# schematic_v2.net
KiCad netlist of a schematic drawn in EAGLE
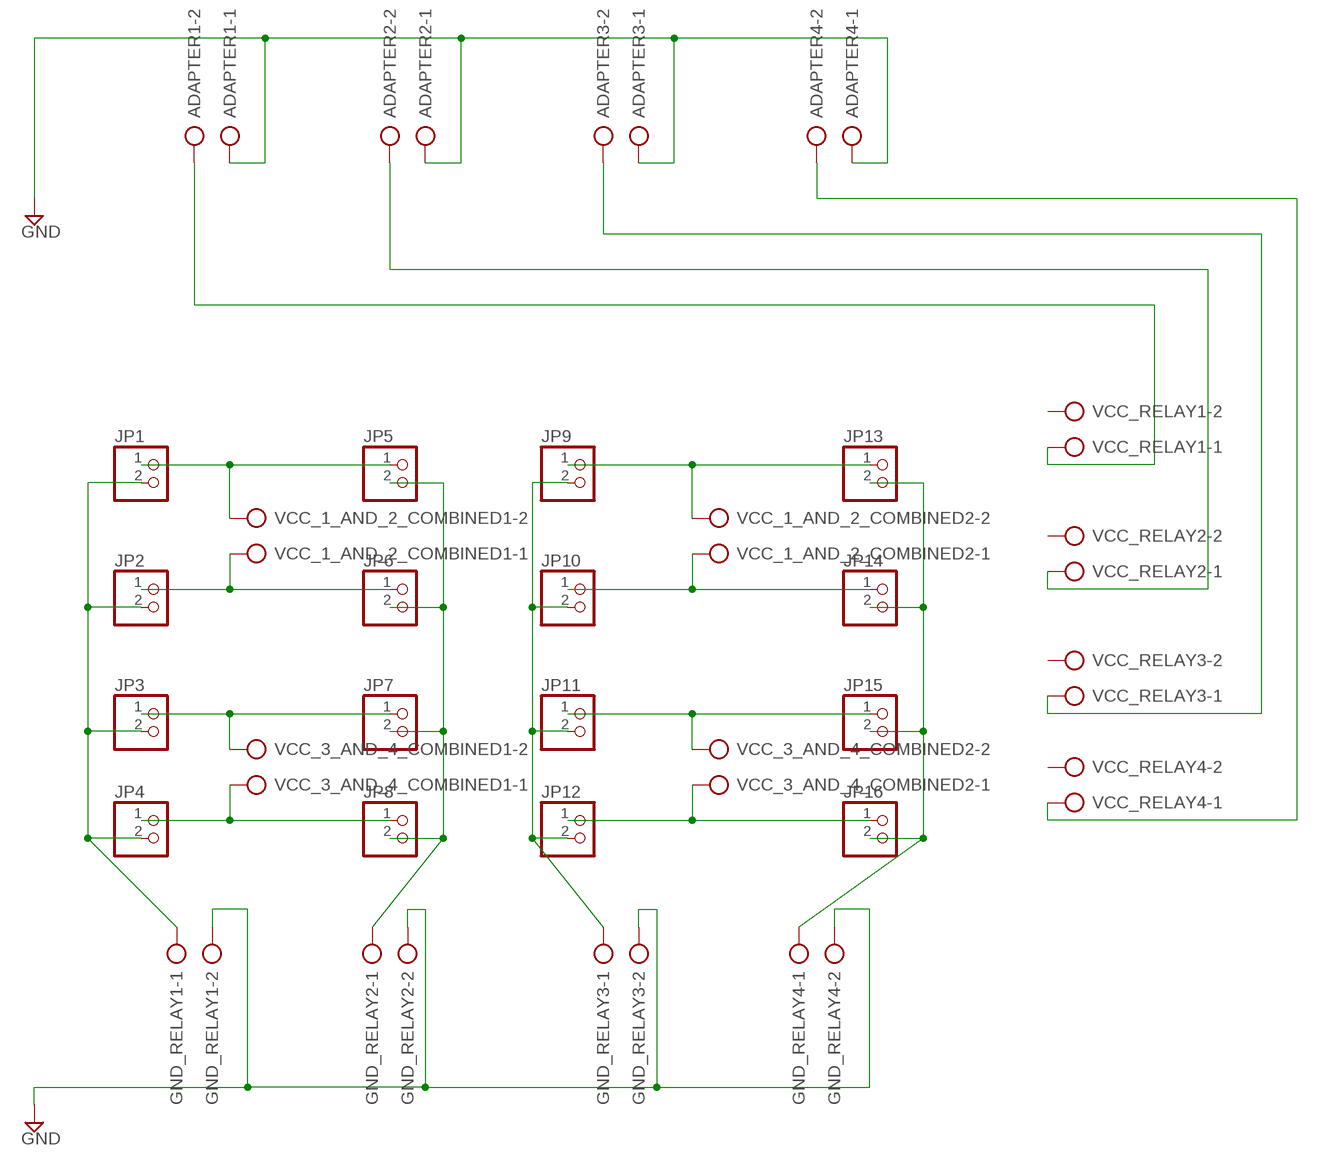
[diagram p0: schematic, sheet 1]

(export (version "E")
  (design (tool "Eeschema 10.0.6"))
  (components
    (comp (ref "ADAPTER1")
      (value "AK300/2")
      (footprint "eagle-import:AK300_2")
      (libsource (lib "eagle-import") (part "AK300/2"))
    )
    (comp (ref "ADAPTER2")
      (value "AK300/2")
      (footprint "eagle-import:AK300_2")
      (libsource (lib "eagle-import") (part "AK300/2"))
    )
    (comp (ref "ADAPTER3")
      (value "AK300/2")
      (footprint "eagle-import:AK300_2")
      (libsource (lib "eagle-import") (part "AK300/2"))
    )
    (comp (ref "ADAPTER4")
      (value "AK300/2")
      (footprint "eagle-import:AK300_2")
      (libsource (lib "eagle-import") (part "AK300/2"))
    )
    (comp (ref "GND_RELAY1")
      (value "AK300/2")
      (footprint "eagle-import:AK300_2")
      (libsource (lib "eagle-import") (part "AK300/2"))
    )
    (comp (ref "GND_RELAY2")
      (value "AK300/2")
      (footprint "eagle-import:AK300_2")
      (libsource (lib "eagle-import") (part "AK300/2"))
    )
    (comp (ref "GND_RELAY3")
      (value "AK300/2")
      (footprint "eagle-import:AK300_2")
      (libsource (lib "eagle-import") (part "AK300/2"))
    )
    (comp (ref "GND_RELAY4")
      (value "AK300/2")
      (footprint "eagle-import:AK300_2")
      (libsource (lib "eagle-import") (part "AK300/2"))
    )
    (comp (ref "JP1")
      (value "PINHD-1X2")
      (footprint "eagle-import:1X02")
      (libsource (lib "eagle-import") (part "PINHD-1X2"))
    )
    (comp (ref "JP2")
      (value "PINHD-1X2")
      (footprint "eagle-import:1X02")
      (libsource (lib "eagle-import") (part "PINHD-1X2"))
    )
    (comp (ref "JP3")
      (value "PINHD-1X2")
      (footprint "eagle-import:1X02")
      (libsource (lib "eagle-import") (part "PINHD-1X2"))
    )
    (comp (ref "JP4")
      (value "PINHD-1X2")
      (footprint "eagle-import:1X02")
      (libsource (lib "eagle-import") (part "PINHD-1X2"))
    )
    (comp (ref "JP5")
      (value "PINHD-1X2")
      (footprint "eagle-import:1X02")
      (libsource (lib "eagle-import") (part "PINHD-1X2"))
    )
    (comp (ref "JP6")
      (value "PINHD-1X2")
      (footprint "eagle-import:1X02")
      (libsource (lib "eagle-import") (part "PINHD-1X2"))
    )
    (comp (ref "JP7")
      (value "PINHD-1X2")
      (footprint "eagle-import:1X02")
      (libsource (lib "eagle-import") (part "PINHD-1X2"))
    )
    (comp (ref "JP8")
      (value "PINHD-1X2")
      (footprint "eagle-import:1X02")
      (libsource (lib "eagle-import") (part "PINHD-1X2"))
    )
    (comp (ref "JP9")
      (value "PINHD-1X2")
      (footprint "eagle-import:1X02")
      (libsource (lib "eagle-import") (part "PINHD-1X2"))
    )
    (comp (ref "JP10")
      (value "PINHD-1X2")
      (footprint "eagle-import:1X02")
      (libsource (lib "eagle-import") (part "PINHD-1X2"))
    )
    (comp (ref "JP11")
      (value "PINHD-1X2")
      (footprint "eagle-import:1X02")
      (libsource (lib "eagle-import") (part "PINHD-1X2"))
    )
    (comp (ref "JP12")
      (value "PINHD-1X2")
      (footprint "eagle-import:1X02")
      (libsource (lib "eagle-import") (part "PINHD-1X2"))
    )
    (comp (ref "JP13")
      (value "PINHD-1X2")
      (footprint "eagle-import:1X02")
      (libsource (lib "eagle-import") (part "PINHD-1X2"))
    )
    (comp (ref "JP14")
      (value "PINHD-1X2")
      (footprint "eagle-import:1X02")
      (libsource (lib "eagle-import") (part "PINHD-1X2"))
    )
    (comp (ref "JP15")
      (value "PINHD-1X2")
      (footprint "eagle-import:1X02")
      (libsource (lib "eagle-import") (part "PINHD-1X2"))
    )
    (comp (ref "JP16")
      (value "PINHD-1X2")
      (footprint "eagle-import:1X02")
      (libsource (lib "eagle-import") (part "PINHD-1X2"))
    )
    (comp (ref "VCC_1_AND_2_COMBINED1")
      (value "AK300/2")
      (footprint "eagle-import:AK300_2")
      (libsource (lib "eagle-import") (part "AK300/2"))
    )
    (comp (ref "VCC_1_AND_2_COMBINED2")
      (value "AK300/2")
      (footprint "eagle-import:AK300_2")
      (libsource (lib "eagle-import") (part "AK300/2"))
    )
    (comp (ref "VCC_3_AND_4_COMBINED1")
      (value "AK300/2")
      (footprint "eagle-import:AK300_2")
      (libsource (lib "eagle-import") (part "AK300/2"))
    )
    (comp (ref "VCC_3_AND_4_COMBINED2")
      (value "AK300/2")
      (footprint "eagle-import:AK300_2")
      (libsource (lib "eagle-import") (part "AK300/2"))
    )
    (comp (ref "VCC_RELAY1")
      (value "AK300/2")
      (footprint "eagle-import:AK300_2")
      (libsource (lib "eagle-import") (part "AK300/2"))
    )
    (comp (ref "VCC_RELAY2")
      (value "AK300/2")
      (footprint "eagle-import:AK300_2")
      (libsource (lib "eagle-import") (part "AK300/2"))
    )
    (comp (ref "VCC_RELAY3")
      (value "AK300/2")
      (footprint "eagle-import:AK300_2")
      (libsource (lib "eagle-import") (part "AK300/2"))
    )
    (comp (ref "VCC_RELAY4")
      (value "AK300/2")
      (footprint "eagle-import:AK300_2")
      (libsource (lib "eagle-import") (part "AK300/2"))
    )
  )
  (nets
    (net (code "1") (name "GND") (class "Default")
      (node (ref "ADAPTER1") (pin "1") (pinfunction "KL_1") (pintype "passive"))
      (node (ref "ADAPTER2") (pin "1") (pinfunction "KL_1") (pintype "passive"))
      (node (ref "ADAPTER3") (pin "1") (pinfunction "KL_1") (pintype "passive"))
      (node (ref "ADAPTER4") (pin "1") (pinfunction "KL_1") (pintype "passive"))
      (node (ref "GND_RELAY1") (pin "2") (pinfunction "KL_2") (pintype "passive"))
      (node (ref "GND_RELAY2") (pin "2") (pinfunction "KL_2") (pintype "passive"))
      (node (ref "GND_RELAY3") (pin "2") (pinfunction "KL_2") (pintype "passive"))
      (node (ref "GND_RELAY4") (pin "2") (pinfunction "KL_2") (pintype "passive"))
    )
    (net (code "2") (name "Net-(ADAPTER1B-KL)") (class "Default")
      (node (ref "ADAPTER1") (pin "2") (pinfunction "KL_2") (pintype "passive"))
      (node (ref "VCC_RELAY1") (pin "1") (pinfunction "KL_1") (pintype "passive"))
    )
    (net (code "3") (name "Net-(ADAPTER2B-KL)") (class "Default")
      (node (ref "ADAPTER2") (pin "2") (pinfunction "KL_2") (pintype "passive"))
      (node (ref "VCC_RELAY2") (pin "1") (pinfunction "KL_1") (pintype "passive"))
    )
    (net (code "4") (name "Net-(ADAPTER3B-KL)") (class "Default")
      (node (ref "ADAPTER3") (pin "2") (pinfunction "KL_2") (pintype "passive"))
      (node (ref "VCC_RELAY3") (pin "1") (pinfunction "KL_1") (pintype "passive"))
    )
    (net (code "5") (name "Net-(ADAPTER4B-KL)") (class "Default")
      (node (ref "ADAPTER4") (pin "2") (pinfunction "KL_2") (pintype "passive"))
      (node (ref "VCC_RELAY4") (pin "1") (pinfunction "KL_1") (pintype "passive"))
    )
    (net (code "6") (name "Net-(GND_RELAY1A-KL)") (class "Default")
      (node (ref "GND_RELAY1") (pin "1") (pinfunction "KL_1") (pintype "passive"))
      (node (ref "JP1") (pin "2") (pinfunction "2_2") (pintype "passive"))
      (node (ref "JP2") (pin "2") (pinfunction "2_2") (pintype "passive"))
      (node (ref "JP3") (pin "2") (pinfunction "2_2") (pintype "passive"))
      (node (ref "JP4") (pin "2") (pinfunction "2_2") (pintype "passive"))
    )
    (net (code "7") (name "Net-(GND_RELAY2A-KL)") (class "Default")
      (node (ref "GND_RELAY2") (pin "1") (pinfunction "KL_1") (pintype "passive"))
      (node (ref "JP5") (pin "2") (pinfunction "2_2") (pintype "passive"))
      (node (ref "JP6") (pin "2") (pinfunction "2_2") (pintype "passive"))
      (node (ref "JP7") (pin "2") (pinfunction "2_2") (pintype "passive"))
      (node (ref "JP8") (pin "2") (pinfunction "2_2") (pintype "passive"))
    )
    (net (code "8") (name "Net-(GND_RELAY3A-KL)") (class "Default")
      (node (ref "GND_RELAY3") (pin "1") (pinfunction "KL_1") (pintype "passive"))
      (node (ref "JP10") (pin "2") (pinfunction "2_2") (pintype "passive"))
      (node (ref "JP11") (pin "2") (pinfunction "2_2") (pintype "passive"))
      (node (ref "JP12") (pin "2") (pinfunction "2_2") (pintype "passive"))
      (node (ref "JP9") (pin "2") (pinfunction "2_2") (pintype "passive"))
    )
    (net (code "9") (name "Net-(GND_RELAY4A-KL)") (class "Default")
      (node (ref "GND_RELAY4") (pin "1") (pinfunction "KL_1") (pintype "passive"))
      (node (ref "JP13") (pin "2") (pinfunction "2_2") (pintype "passive"))
      (node (ref "JP14") (pin "2") (pinfunction "2_2") (pintype "passive"))
      (node (ref "JP15") (pin "2") (pinfunction "2_2") (pintype "passive"))
      (node (ref "JP16") (pin "2") (pinfunction "2_2") (pintype "passive"))
    )
    (net (code "10") (name "Net-(VCC_1_AND_2_COMBINED1A-KL)") (class "Default")
      (node (ref "JP2") (pin "1") (pinfunction "1_1") (pintype "passive"))
      (node (ref "JP6") (pin "1") (pinfunction "1_1") (pintype "passive"))
      (node (ref "VCC_1_AND_2_COMBINED1") (pin "1") (pinfunction "KL_1") (pintype "passive"))
    )
    (net (code "11") (name "Net-(VCC_1_AND_2_COMBINED1B-KL)") (class "Default")
      (node (ref "JP1") (pin "1") (pinfunction "1_1") (pintype "passive"))
      (node (ref "JP5") (pin "1") (pinfunction "1_1") (pintype "passive"))
      (node (ref "VCC_1_AND_2_COMBINED1") (pin "2") (pinfunction "KL_2") (pintype "passive"))
    )
    (net (code "12") (name "Net-(VCC_1_AND_2_COMBINED2A-KL)") (class "Default")
      (node (ref "JP10") (pin "1") (pinfunction "1_1") (pintype "passive"))
      (node (ref "JP14") (pin "1") (pinfunction "1_1") (pintype "passive"))
      (node (ref "VCC_1_AND_2_COMBINED2") (pin "1") (pinfunction "KL_1") (pintype "passive"))
    )
    (net (code "13") (name "Net-(VCC_1_AND_2_COMBINED2B-KL)") (class "Default")
      (node (ref "JP13") (pin "1") (pinfunction "1_1") (pintype "passive"))
      (node (ref "JP9") (pin "1") (pinfunction "1_1") (pintype "passive"))
      (node (ref "VCC_1_AND_2_COMBINED2") (pin "2") (pinfunction "KL_2") (pintype "passive"))
    )
    (net (code "14") (name "Net-(VCC_3_AND_4_COMBINED1A-KL)") (class "Default")
      (node (ref "JP4") (pin "1") (pinfunction "1_1") (pintype "passive"))
      (node (ref "JP8") (pin "1") (pinfunction "1_1") (pintype "passive"))
      (node (ref "VCC_3_AND_4_COMBINED1") (pin "1") (pinfunction "KL_1") (pintype "passive"))
    )
    (net (code "15") (name "Net-(VCC_3_AND_4_COMBINED1B-KL)") (class "Default")
      (node (ref "JP3") (pin "1") (pinfunction "1_1") (pintype "passive"))
      (node (ref "JP7") (pin "1") (pinfunction "1_1") (pintype "passive"))
      (node (ref "VCC_3_AND_4_COMBINED1") (pin "2") (pinfunction "KL_2") (pintype "passive"))
    )
    (net (code "16") (name "Net-(VCC_3_AND_4_COMBINED2A-KL)") (class "Default")
      (node (ref "JP12") (pin "1") (pinfunction "1_1") (pintype "passive"))
      (node (ref "JP16") (pin "1") (pinfunction "1_1") (pintype "passive"))
      (node (ref "VCC_3_AND_4_COMBINED2") (pin "1") (pinfunction "KL_1") (pintype "passive"))
    )
    (net (code "17") (name "Net-(VCC_3_AND_4_COMBINED2B-KL)") (class "Default")
      (node (ref "JP11") (pin "1") (pinfunction "1_1") (pintype "passive"))
      (node (ref "JP15") (pin "1") (pinfunction "1_1") (pintype "passive"))
      (node (ref "VCC_3_AND_4_COMBINED2") (pin "2") (pinfunction "KL_2") (pintype "passive"))
    )
    (net (code "18") (name "unconnected-(VCC_RELAY1B-KL-Pad2)") (class "Default")
      (node (ref "VCC_RELAY1") (pin "2") (pinfunction "KL_2") (pintype "passive"))
    )
    (net (code "19") (name "unconnected-(VCC_RELAY2B-KL-Pad2)") (class "Default")
      (node (ref "VCC_RELAY2") (pin "2") (pinfunction "KL_2") (pintype "passive"))
    )
    (net (code "20") (name "unconnected-(VCC_RELAY3B-KL-Pad2)") (class "Default")
      (node (ref "VCC_RELAY3") (pin "2") (pinfunction "KL_2") (pintype "passive"))
    )
    (net (code "21") (name "unconnected-(VCC_RELAY4B-KL-Pad2)") (class "Default")
      (node (ref "VCC_RELAY4") (pin "2") (pinfunction "KL_2") (pintype "passive"))
    )
  )
)
